# Schematic.net
KiCad netlist of a schematic drawn in Altium Designer
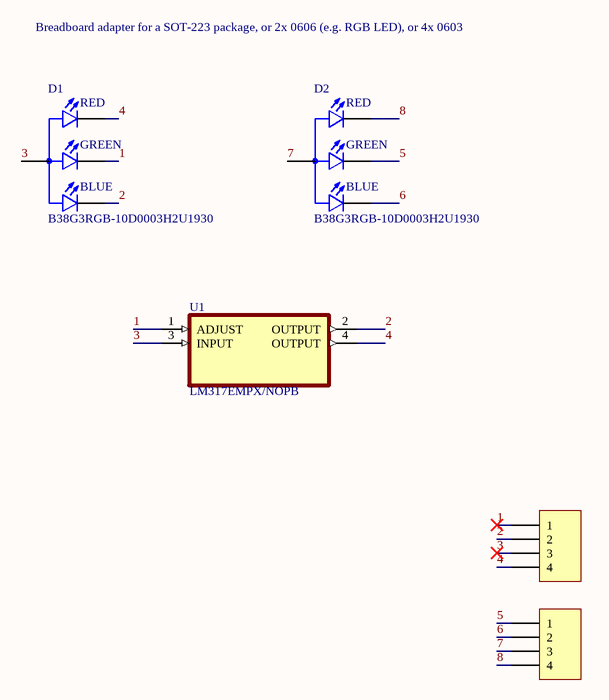
[diagram p0: Schematic.SchDoc]

(export (version "E")
  (design (tool "Eeschema 10.0.6"))
  (components
    (comp (ref "D1")
      (value "B38G3RGB-10D0003H2U1930")
      (footprint "LED_B38G3RGB-10D0003H2U1930")
      (description "Red, Green, Blue (RGB) - LED Indication - Discrete 2V Red, 3V Green, 3V Blue 0606 (1616 Metric)")
      (fields (field (name "MF") "Harvatek Corporation"))
      (libsource (lib "B38G3RGB-10D0003H2U1930") (part "B38G3RGB-10D0003H2U1930"))
    )
    (comp (ref "D2")
      (value "B38G3RGB-10D0003H2U1930")
      (footprint "LED_B38G3RGB-10D0003H2U1930")
      (description "Red, Green, Blue (RGB) - LED Indication - Discrete 2V Red, 3V Green, 3V Blue 0606 (1616 Metric)")
      (fields (field (name "MF") "Harvatek Corporation"))
      (libsource (lib "B38G3RGB-10D0003H2U1930") (part "B38G3RGB-10D0003H2U1930"))
    )
    (comp (ref "P1")
      (value "Header 4")
      (footprint "HDR1X4")
      (description "Header, 4-Pin")
      (fields (field (name "PUBLISHER") "Altium Limited"))
      (libsource (lib "Miscellaneous Connectors") (part "Header 4"))
    )
    (comp (ref "P2")
      (value "Header 4")
      (footprint "HDR1X4")
      (description "Header, 4-Pin")
      (fields (field (name "PUBLISHER") "Altium Limited"))
      (libsource (lib "Miscellaneous Connectors") (part "Header 4"))
    )
    (comp (ref "U1")
      (value "LM317EMPX/NOPB")
      (footprint "SOT230P700X180-4N")
      (description "1.5-A, 40-V, adjustable linear voltage regulator 4-SOT-223 0 to 125")
      (fields (field (name "MF") "Texas Instruments"))
      (libsource (lib "LM317EMPX_NOPB") (part "LM317EMPX/NOPB"))
    )
  )
  (nets
    (net (code "1") (name "/1") (class "Default")
      (node (ref "D1") (pin "1") (pinfunction "G_C_1") (pintype "passive"))
      (node (ref "P1") (pin "1") (pinfunction "1_1") (pintype "passive"))
      (node (ref "U1") (pin "1") (pinfunction "ADJUST_1") (pintype "input"))
    )
    (net (code "2") (name "/2") (class "Default")
      (node (ref "D1") (pin "2") (pinfunction "B_C_2") (pintype "passive"))
      (node (ref "P1") (pin "2") (pinfunction "2_2") (pintype "passive"))
      (node (ref "U1") (pin "2") (pinfunction "OUTPUT_2") (pintype "output"))
    )
    (net (code "3") (name "/3") (class "Default")
      (node (ref "D1") (pin "3") (pinfunction "A_3") (pintype "passive"))
      (node (ref "P1") (pin "3") (pinfunction "3_3") (pintype "passive"))
      (node (ref "U1") (pin "3") (pinfunction "INPUT_3") (pintype "input"))
    )
    (net (code "4") (name "/4") (class "Default")
      (node (ref "D1") (pin "4") (pinfunction "R_C_4") (pintype "passive"))
      (node (ref "P1") (pin "4") (pinfunction "4_4") (pintype "passive"))
      (node (ref "U1") (pin "4") (pinfunction "OUTPUT_4") (pintype "output"))
    )
    (net (code "5") (name "/5") (class "Default")
      (node (ref "D2") (pin "1") (pinfunction "G_C_1") (pintype "passive"))
      (node (ref "P2") (pin "1") (pinfunction "1_1") (pintype "passive"))
    )
    (net (code "6") (name "/6") (class "Default")
      (node (ref "D2") (pin "2") (pinfunction "B_C_2") (pintype "passive"))
      (node (ref "P2") (pin "2") (pinfunction "2_2") (pintype "passive"))
    )
    (net (code "7") (name "/7") (class "Default")
      (node (ref "D2") (pin "3") (pinfunction "A_3") (pintype "passive"))
      (node (ref "P2") (pin "3") (pinfunction "3_3") (pintype "passive"))
    )
    (net (code "8") (name "/8") (class "Default")
      (node (ref "D2") (pin "4") (pinfunction "R_C_4") (pintype "passive"))
      (node (ref "P2") (pin "4") (pinfunction "4_4") (pintype "passive"))
    )
  )
)
